# Float_Power_PCB.net
KiCad netlist of a schematic drawn in Altium Designer
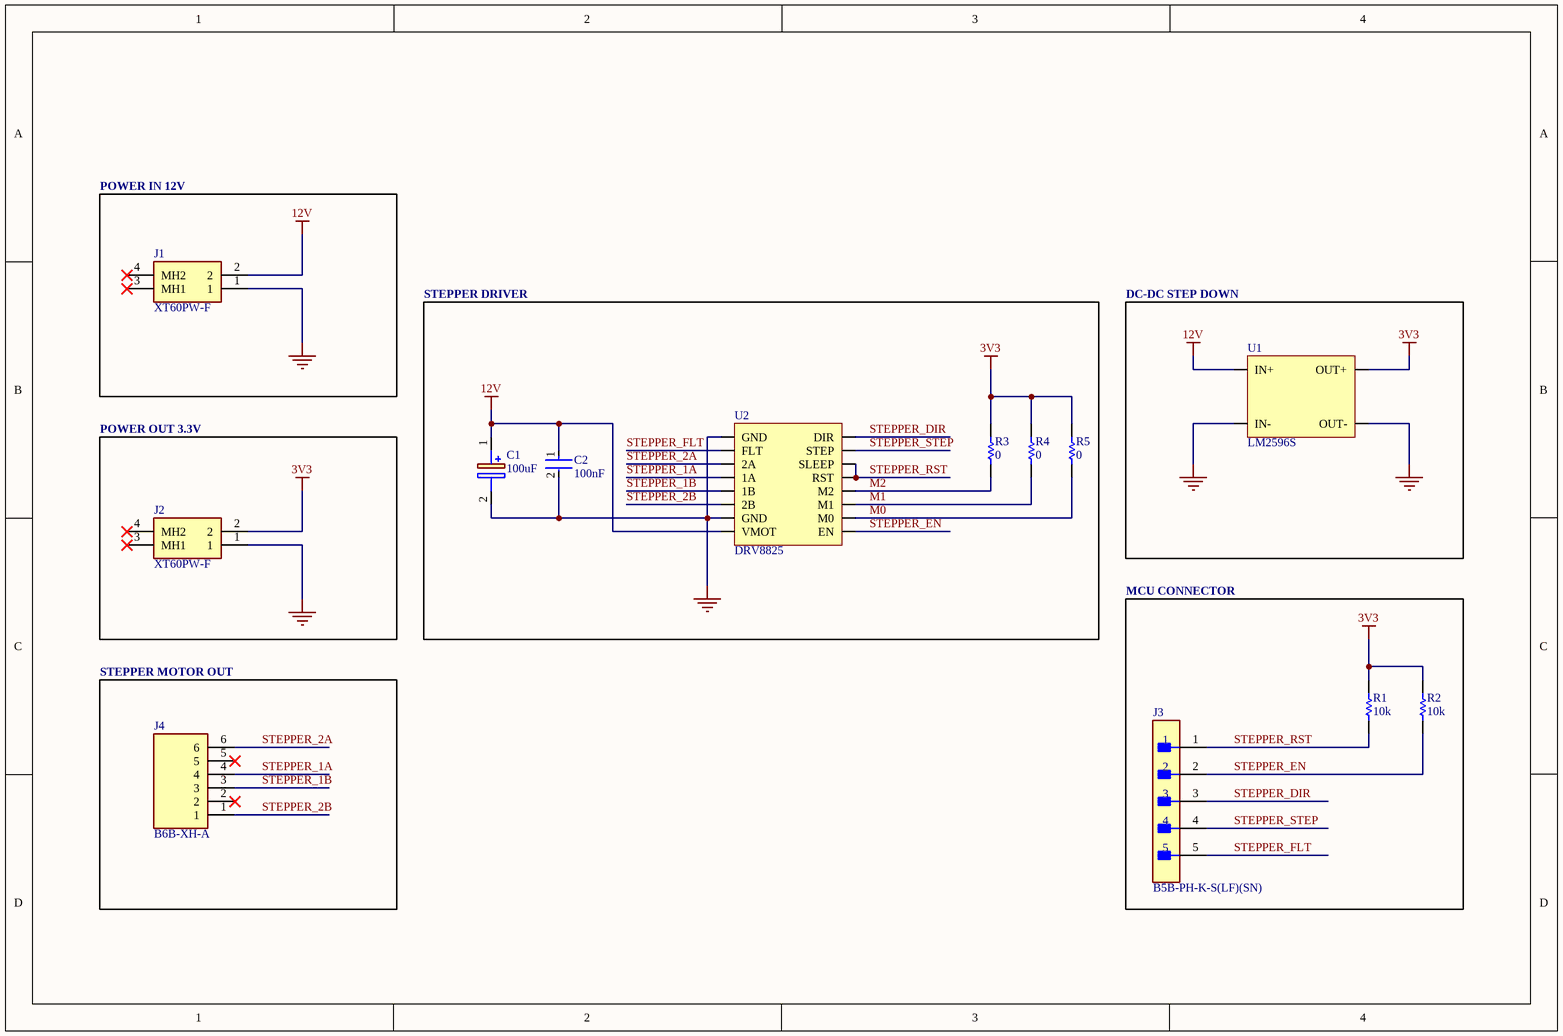
[diagram p0: Float_Power_PCB.SchDoc]

(export (version "E")
  (design (tool "Eeschema 10.0.6"))
  (components
    (comp (ref "C1")
      (value "100uF")
      (footprint "SamacSys:EEHZA1E101XP")
      (description "Capacitor Polarised")
      (fields (field (name "MANUFACTURER_PART_NUMBER") "EEHZA1E101XP"))
      (libsource (lib "*") (part "EEHZA1E101XP"))
    )
    (comp (ref "C2")
      (value "100nF")
      (footprint "FP-0805-L_2_01_0_2-W_1_25-MFG")
      (fields (field (name "TOLERANCE") "10%") (field (name "VOLTAGE") "10V"))
      (libsource (lib "Altium Content Vault") (part "b4654b650e69147ec39a6b967a45e02"))
    )
    (comp (ref "J1")
      (value "XT60PW-F")
      (footprint "SamacSys:XT60PWF")
      (description "Connector")
      (libsource (lib "*") (part "XT60PW-F"))
    )
    (comp (ref "J2")
      (value "XT60PW-F")
      (footprint "SamacSys:XT60PWF")
      (description "Connector")
      (libsource (lib "*") (part "XT60PW-F"))
    )
    (comp (ref "J3")
      (value "B5B-PH-K-S(LF)(SN)")
      (footprint "FP-B5B-PH-K-S_LF_SN-MFG")
      (description "CONN HEADER VERT 5POS 2MM")
      (libsource (lib "Altium Content Vault") (part "bf93c07fd2649a848d0ec8585582aab"))
    )
    (comp (ref "J4")
      (value "B6B-XH-A")
      (footprint "SamacSys:B6BXHA")
      (description "Connector")
      (libsource (lib "*") (part "B6B-XH-A"))
    )
    (comp (ref "R1")
      (value "10k")
      (footprint "RESC2013X60X35ML10T20")
      (fields (field (name "TOLERANCE") "1%") (field (name "MANUFACTURER") "Yageo"))
      (libsource (lib "Altium Content Vault") (part "RES-2"))
    )
    (comp (ref "R2")
      (value "10k")
      (footprint "RESC2013X60X35ML10T20")
      (fields (field (name "TOLERANCE") "1%") (field (name "MANUFACTURER") "Yageo"))
      (libsource (lib "Altium Content Vault") (part "RES-2"))
    )
    (comp (ref "R3")
      (value "0")
      (footprint "RESC2013X60X35ML10T20")
      (fields (field (name "TOLERANCE") "1%") (field (name "MANUFACTURER") "Yageo"))
      (libsource (lib "Altium Content Vault") (part "RES-2"))
    )
    (comp (ref "R4")
      (value "0")
      (footprint "RESC2013X60X35ML10T20")
      (fields (field (name "TOLERANCE") "1%") (field (name "MANUFACTURER") "Yageo"))
      (libsource (lib "Altium Content Vault") (part "RES-2"))
    )
    (comp (ref "R5")
      (value "0")
      (footprint "RESC2013X60X35ML10T20")
      (fields (field (name "TOLERANCE") "1%") (field (name "MANUFACTURER") "Yageo"))
      (libsource (lib "Altium Content Vault") (part "RES-2"))
    )
    (comp (ref "U1")
      (value "LM2596S")
      (footprint "LM2596S")
      (description "LM2596S DC-DC Buck Converter: step-down voltage regulator, 3A max, 1.23–37V output")
      (libsource (lib "Drivers") (part "LM2596S"))
    )
    (comp (ref "U2")
      (value "DRV8825")
      (footprint "DRV8825")
      (description "DRV8825 stepper motor driver module")
      (libsource (lib "Drivers") (part "DRV8825"))
    )
  )
  (nets
    (net (code "1") (name "/M0") (class "Default")
      (node (ref "R5") (pin "1") (pinfunction "1_1") (pintype "passive"))
      (node (ref "U2") (pin "M0") (pinfunction "M0_M0") (pintype "passive"))
    )
    (net (code "2") (name "/M1") (class "Default")
      (node (ref "R4") (pin "1") (pinfunction "1_1") (pintype "passive"))
      (node (ref "U2") (pin "M1") (pinfunction "M1_M1") (pintype "passive"))
    )
    (net (code "3") (name "/M2") (class "Default")
      (node (ref "R3") (pin "2") (pinfunction "2_2") (pintype "passive"))
      (node (ref "U2") (pin "M2") (pinfunction "M2_M2") (pintype "passive"))
    )
    (net (code "4") (name "/STEPPER_1A") (class "Default")
      (node (ref "J4") (pin "4") (pinfunction "4_4") (pintype "passive"))
      (node (ref "U2") (pin "1A") (pinfunction "1A_1A") (pintype "passive"))
    )
    (net (code "5") (name "/STEPPER_1B") (class "Default")
      (node (ref "J4") (pin "3") (pinfunction "3_3") (pintype "passive"))
      (node (ref "U2") (pin "1B") (pinfunction "1B_1B") (pintype "passive"))
    )
    (net (code "6") (name "/STEPPER_2A") (class "Default")
      (node (ref "J4") (pin "6") (pinfunction "6_6") (pintype "passive"))
      (node (ref "U2") (pin "2A") (pinfunction "2A_2A") (pintype "passive"))
    )
    (net (code "7") (name "/STEPPER_2B") (class "Default")
      (node (ref "J4") (pin "1") (pinfunction "1_1") (pintype "passive"))
      (node (ref "U2") (pin "2B") (pinfunction "2B_2B") (pintype "passive"))
    )
    (net (code "8") (name "/STEPPER_DIR") (class "Default")
      (node (ref "J3") (pin "3") (pinfunction "3_3") (pintype "passive"))
      (node (ref "U2") (pin "DIR") (pinfunction "DIR_DIR") (pintype "passive"))
    )
    (net (code "9") (name "/STEPPER_EN") (class "Default")
      (node (ref "J3") (pin "2") (pinfunction "2_2") (pintype "passive"))
      (node (ref "R2") (pin "1") (pinfunction "1_1") (pintype "passive"))
      (node (ref "U2") (pin "EN") (pinfunction "EN_EN") (pintype "passive"))
    )
    (net (code "10") (name "/STEPPER_FLT") (class "Default")
      (node (ref "J3") (pin "5") (pinfunction "5_5") (pintype "passive"))
      (node (ref "U2") (pin "FLT") (pinfunction "FLT_FLT") (pintype "passive"))
    )
    (net (code "11") (name "/STEPPER_RST") (class "Default")
      (node (ref "J3") (pin "1") (pinfunction "1_1") (pintype "passive"))
      (node (ref "R1") (pin "1") (pinfunction "1_1") (pintype "passive"))
      (node (ref "U2") (pin "RST") (pinfunction "RST_RST") (pintype "passive"))
      (node (ref "U2") (pin "SLEEP") (pinfunction "SLEEP_SLEEP") (pintype "passive"))
    )
    (net (code "12") (name "/STEPPER_STEP") (class "Default")
      (node (ref "J3") (pin "4") (pinfunction "4_4") (pintype "passive"))
      (node (ref "U2") (pin "STEP") (pinfunction "STEP_STEP") (pintype "passive"))
    )
    (net (code "13") (name "3V3") (class "Default")
      (node (ref "J2") (pin "2") (pinfunction "2_2") (pintype "passive"))
      (node (ref "R1") (pin "2") (pinfunction "2_2") (pintype "passive"))
      (node (ref "R2") (pin "2") (pinfunction "2_2") (pintype "passive"))
      (node (ref "R3") (pin "1") (pinfunction "1_1") (pintype "passive"))
      (node (ref "R4") (pin "2") (pinfunction "2_2") (pintype "passive"))
      (node (ref "R5") (pin "2") (pinfunction "2_2") (pintype "passive"))
      (node (ref "U1") (pin "OUT+") (pinfunction "OUT+_OUT+") (pintype "passive"))
    )
    (net (code "14") (name "12V") (class "Default")
      (node (ref "C1") (pin "1") (pinfunction "+_1") (pintype "passive"))
      (node (ref "C2") (pin "1") (pinfunction "1_1") (pintype "passive"))
      (node (ref "J1") (pin "2") (pinfunction "2_2") (pintype "passive"))
      (node (ref "U1") (pin "IN+") (pinfunction "IN+_IN+") (pintype "passive"))
      (node (ref "U2") (pin "VMOT") (pinfunction "VMOT_VMOT") (pintype "passive"))
    )
    (net (code "15") (name "GND") (class "Default")
      (node (ref "C1") (pin "2") (pinfunction "-_2") (pintype "passive"))
      (node (ref "C2") (pin "2") (pinfunction "2_2") (pintype "passive"))
      (node (ref "J1") (pin "1") (pinfunction "1_1") (pintype "passive"))
      (node (ref "J2") (pin "1") (pinfunction "1_1") (pintype "passive"))
      (node (ref "U1") (pin "IN-") (pinfunction "IN-_IN-") (pintype "passive"))
      (node (ref "U1") (pin "OUT-") (pinfunction "OUT-_OUT-") (pintype "passive"))
      (node (ref "U2") (pin "GND") (pinfunction "GND_GND") (pintype "passive"))
    )
    (net (code "16") (name "unconnected-(J1-MH1-Pad3)") (class "Default")
      (node (ref "J1") (pin "3") (pinfunction "MH1_3") (pintype "passive+no_connect"))
    )
    (net (code "17") (name "unconnected-(J1-MH2-Pad4)") (class "Default")
      (node (ref "J1") (pin "4") (pinfunction "MH2_4") (pintype "passive+no_connect"))
    )
    (net (code "18") (name "unconnected-(J2-MH1-Pad3)") (class "Default")
      (node (ref "J2") (pin "3") (pinfunction "MH1_3") (pintype "passive+no_connect"))
    )
    (net (code "19") (name "unconnected-(J2-MH2-Pad4)") (class "Default")
      (node (ref "J2") (pin "4") (pinfunction "MH2_4") (pintype "passive+no_connect"))
    )
    (net (code "20") (name "unconnected-(J4-Pad2)") (class "Default")
      (node (ref "J4") (pin "2") (pinfunction "2_2") (pintype "passive+no_connect"))
    )
    (net (code "21") (name "unconnected-(J4-Pad5)") (class "Default")
      (node (ref "J4") (pin "5") (pinfunction "5_5") (pintype "passive+no_connect"))
    )
  )
)
